# myStrava.net
KiCad netlist of a schematic drawn in EAGLE
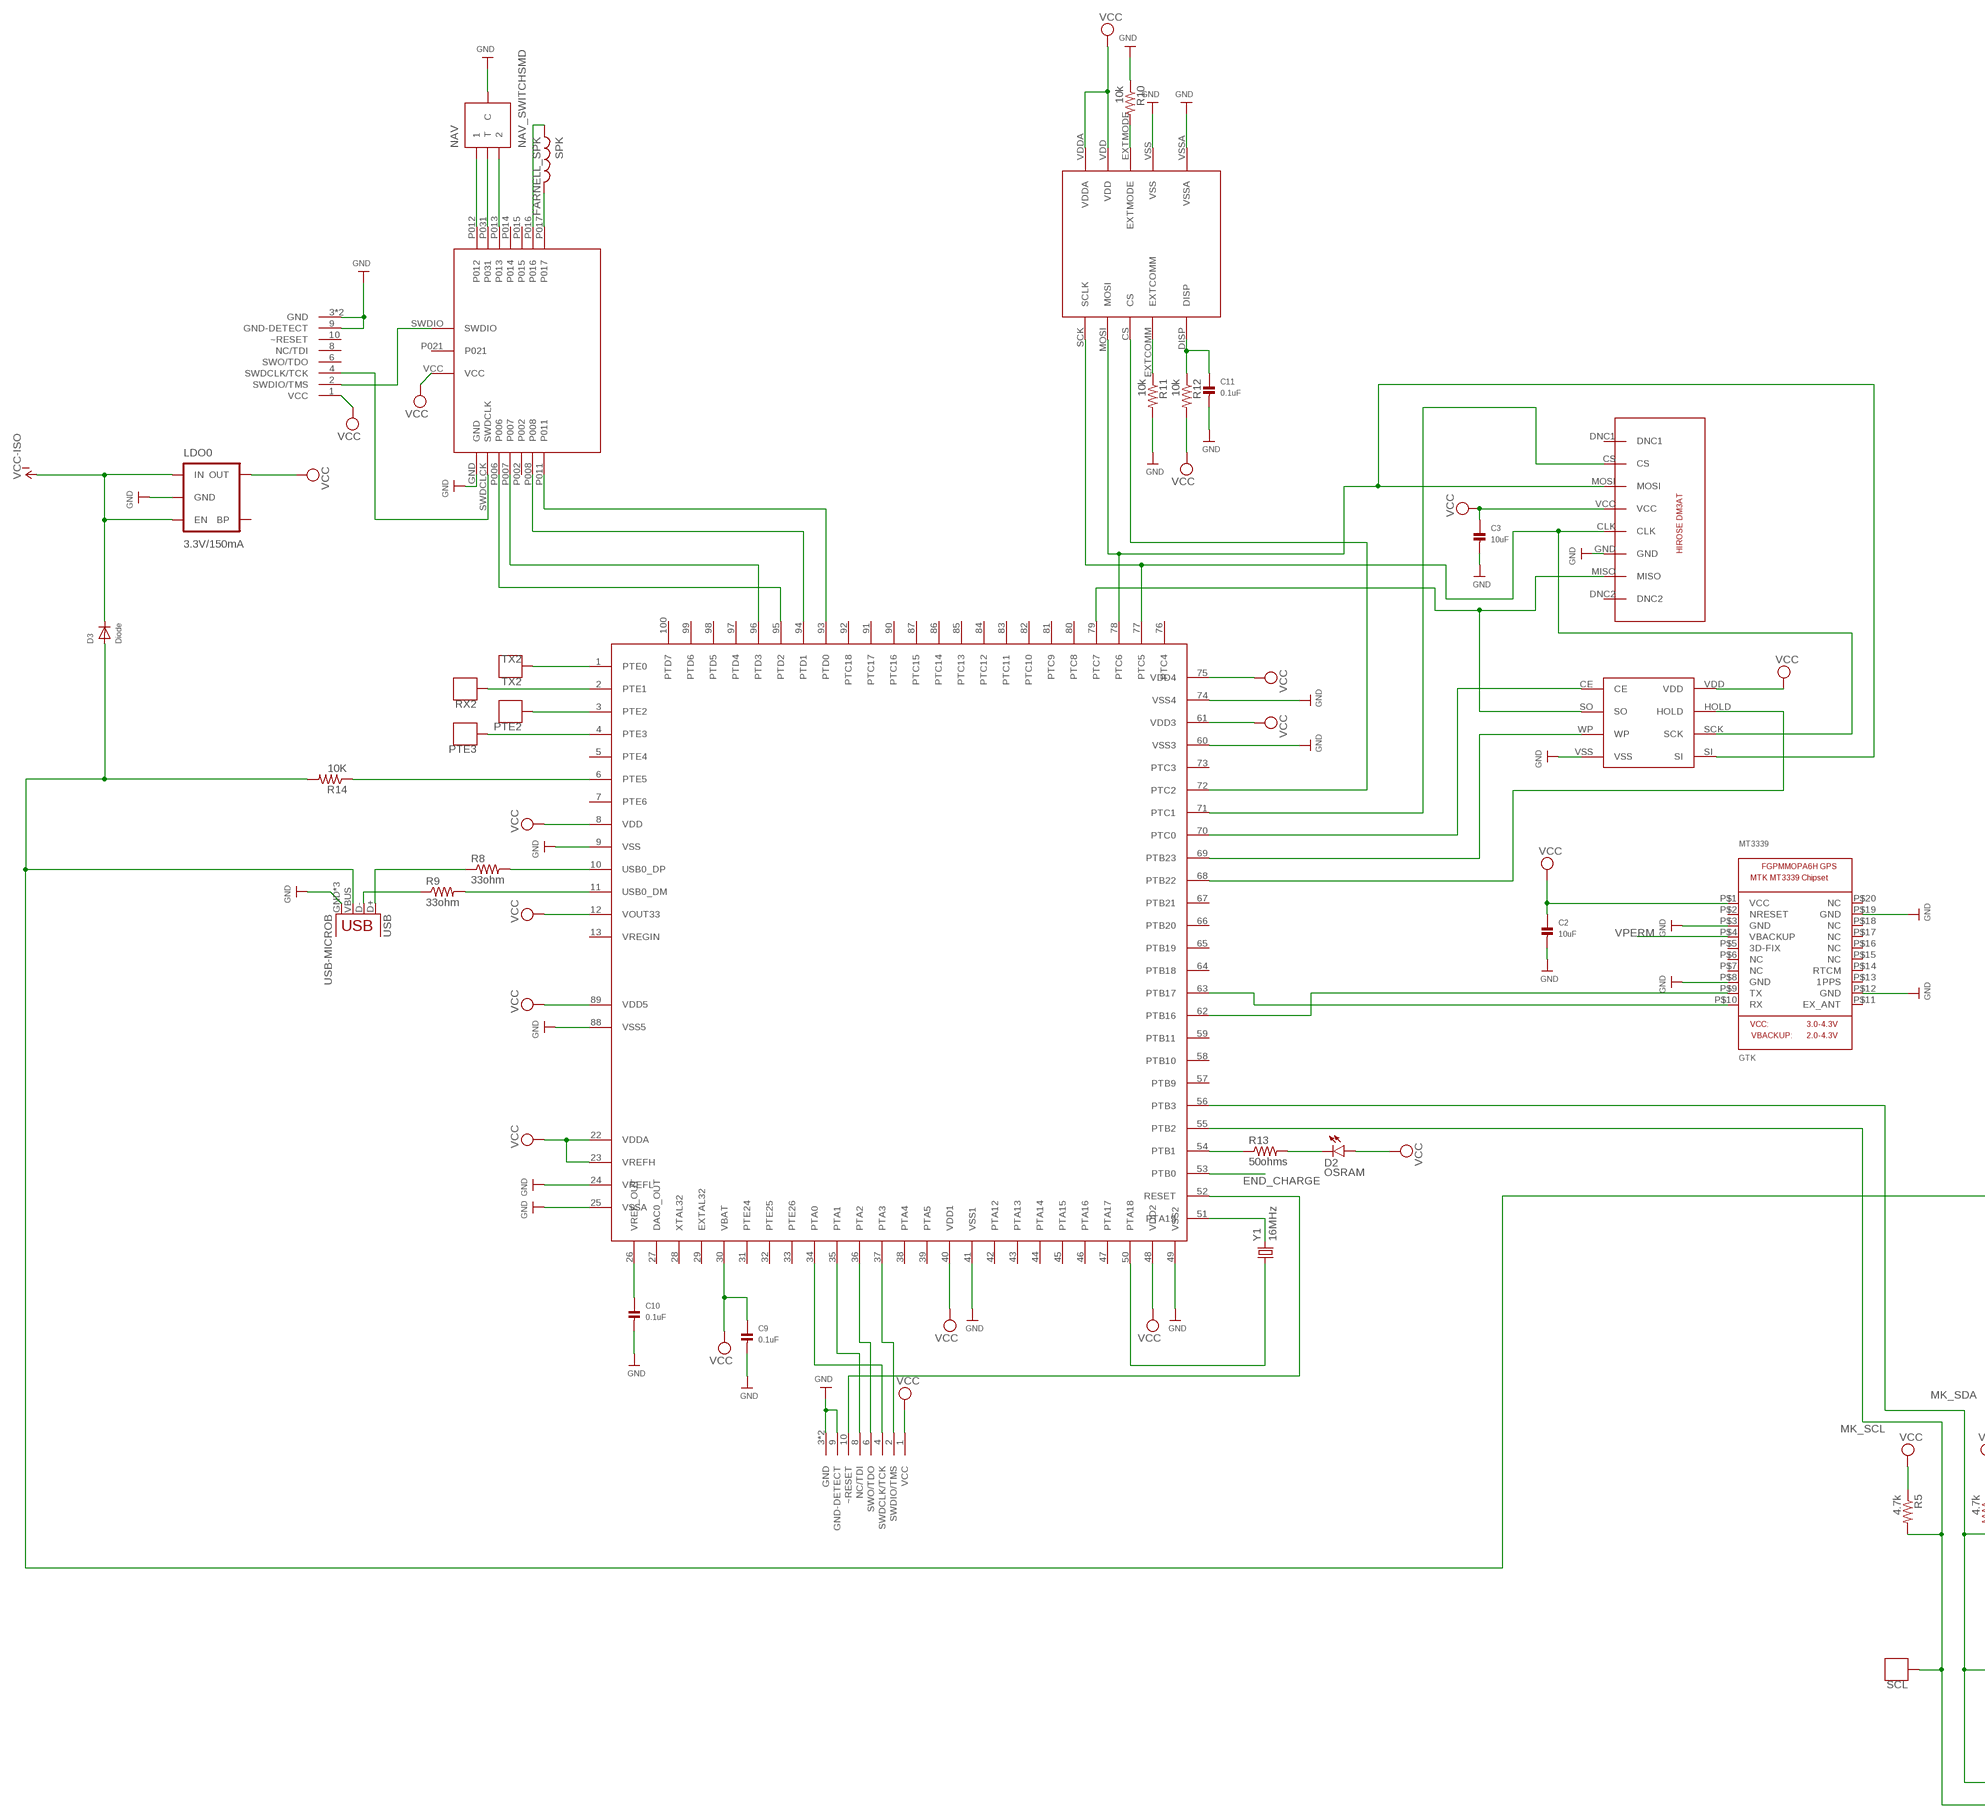
[diagram p0: schematic, sheet 1, part 1 of 2]
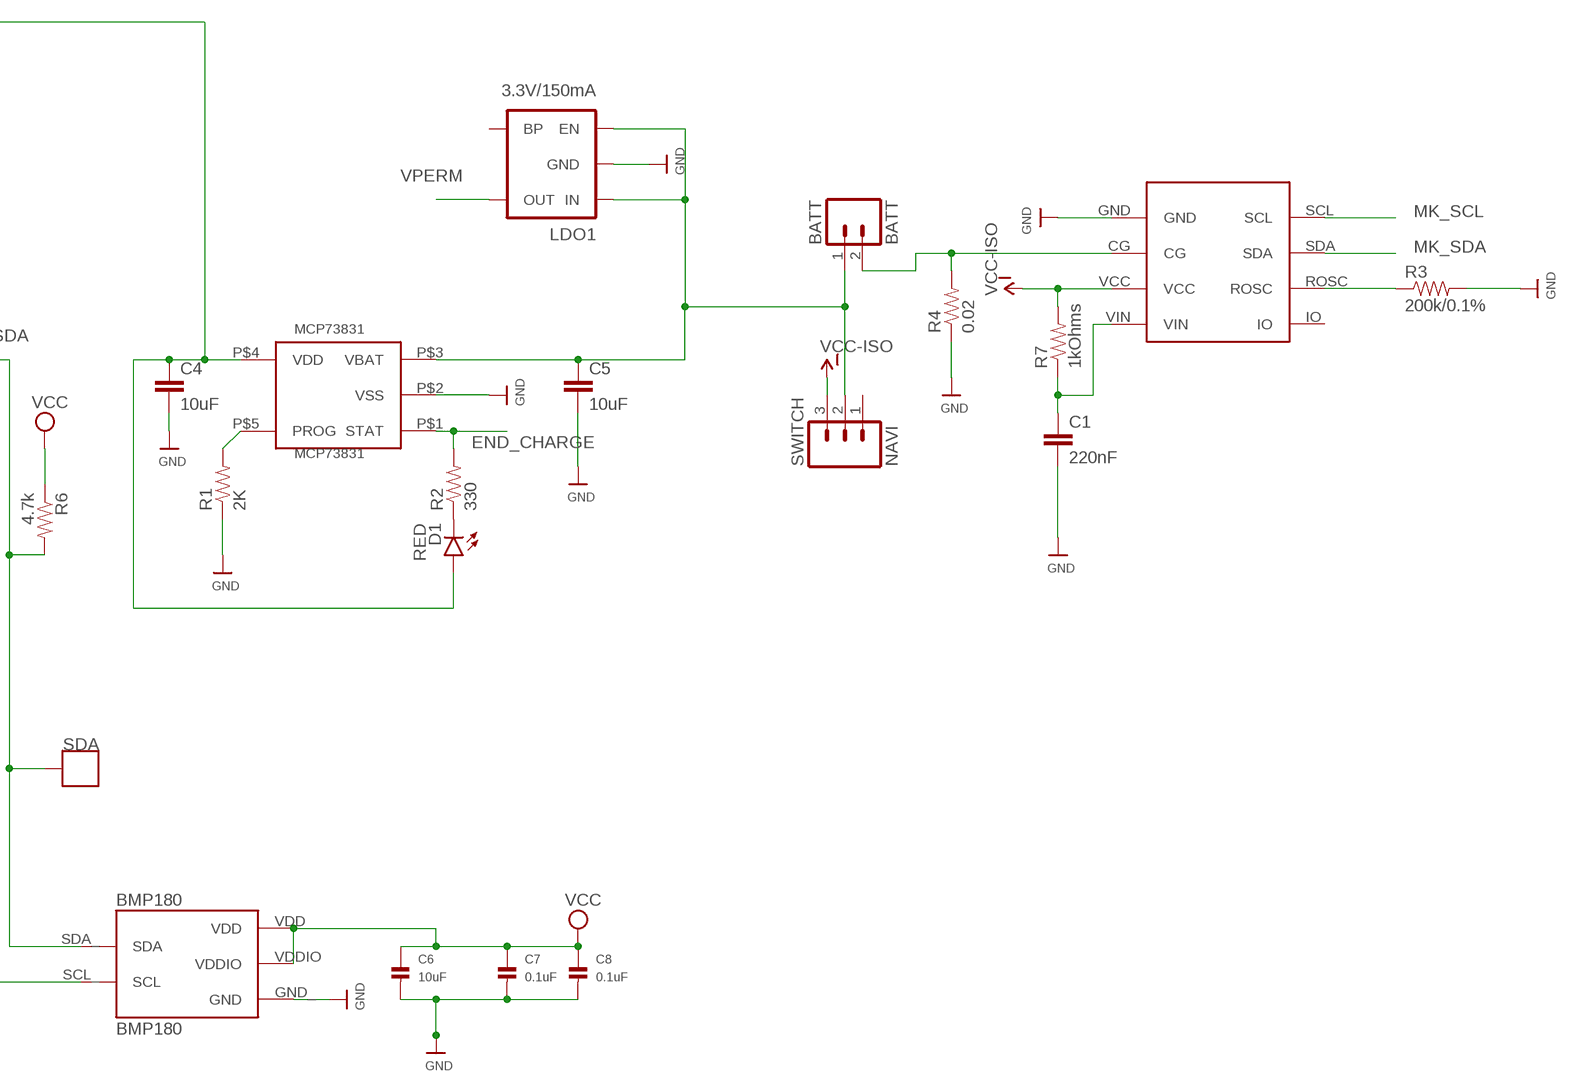
[diagram p1: schematic, sheet 1, part 2 of 2]

(export (version "E")
  (design (tool "Eeschema 10.0.6"))
  (components
    (comp (ref "BATT")
      (value "BATT")
      (footprint "eagle-import:1X02_LONGPADS")
      (libsource (lib "eagle-import") (part "M02PTH3"))
    )
    (comp (ref "BMP180")
      (value "BMP180")
      (footprint "eagle-import:BMP180")
      (libsource (lib "eagle-import") (part "BMP180"))
    )
    (comp (ref "C1")
      (value "220nF")
      (footprint "eagle-import:1206")
      (libsource (lib "eagle-import") (part "10UF-6.3V-20%(1206)"))
    )
    (comp (ref "C2")
      (value "10uF")
      (footprint "eagle-import:1206")
      (libsource (lib "eagle-import") (part "CAP_CERAMIC1206"))
    )
    (comp (ref "C3")
      (value "10uF")
      (footprint "eagle-import:1206")
      (libsource (lib "eagle-import") (part "CAP_CERAMIC1206"))
    )
    (comp (ref "C4")
      (value "10uF")
      (footprint "eagle-import:1206")
      (libsource (lib "eagle-import") (part "10UF-6.3V-20%(1206)"))
    )
    (comp (ref "C5")
      (value "10uF")
      (footprint "eagle-import:1206")
      (libsource (lib "eagle-import") (part "10UF-6.3V-20%(1206)"))
    )
    (comp (ref "C6")
      (value "10uF")
      (footprint "eagle-import:1206")
      (libsource (lib "eagle-import") (part "CAP_CERAMIC1206"))
    )
    (comp (ref "C7")
      (value "0.1uF")
      (footprint "eagle-import:1206")
      (libsource (lib "eagle-import") (part "CAP_CERAMIC1206"))
    )
    (comp (ref "C8")
      (value "0.1uF")
      (footprint "eagle-import:1206")
      (libsource (lib "eagle-import") (part "CAP_CERAMIC1206"))
    )
    (comp (ref "C9")
      (value "0.1uF")
      (footprint "eagle-import:1206")
      (libsource (lib "eagle-import") (part "CAP_CERAMIC1206"))
    )
    (comp (ref "C10")
      (value "0.1uF")
      (footprint "eagle-import:1206")
      (libsource (lib "eagle-import") (part "CAP_CERAMIC1206"))
    )
    (comp (ref "C11")
      (value "0.1uF")
      (footprint "eagle-import:1206")
      (libsource (lib "eagle-import") (part "CAP_CERAMIC1206"))
    )
    (comp (ref "D1")
      (value "RED")
      (footprint "eagle-import:LED-1206")
      (libsource (lib "eagle-import") (part "LED-RED1206"))
    )
    (comp (ref "D2")
      (value "OSRAM")
      (footprint "eagle-import:LED-1206")
      (libsource (lib "eagle-import") (part "LED-RED1206"))
    )
    (comp (ref "D3")
      (value "Diode")
      (footprint "eagle-import:SOD-123FL")
      (libsource (lib "eagle-import") (part "DIODE_SOD-123FL"))
    )
    (comp (ref "JTAG")
      (value "2X5_0.05\"_CORTEX_DEBUGTH_NOKEY_UNSHROUDED")
      (footprint "eagle-import:2X5_0.05__TH_NS")
      (libsource (lib "eagle-import") (part "2X5_0.05{dblquote}_CORTEX_DEBUGTH_NOKEY_UNSHROUDED"))
    )
    (comp (ref "JTAG1")
      (value "2X5_0.05\"_CORTEX_DEBUGTH_NOKEY_UNSHROUDED")
      (footprint "eagle-import:2X5_0.05__TH_NS")
      (libsource (lib "eagle-import") (part "2X5_0.05{dblquote}_CORTEX_DEBUGTH_NOKEY_UNSHROUDED"))
    )
    (comp (ref "LDO0")
      (value "3.3V/150mA")
      (footprint "eagle-import:SOT23-5")
      (libsource (lib "eagle-import") (part "V_REG_MIC52053.3V"))
    )
    (comp (ref "LDO1")
      (value "3.3V/150mA")
      (footprint "eagle-import:SOT23-5")
      (libsource (lib "eagle-import") (part "V_REG_MIC52053.3V"))
    )
    (comp (ref "MCP73831")
      (value "MCP73831")
      (footprint "eagle-import:5PIN_SOT23")
      (libsource (lib "eagle-import") (part "MCP73831"))
    )
    (comp (ref "MK20DN512")
      (value "MK20DN512")
      (footprint "eagle-import:LQFP-100")
      (libsource (lib "eagle-import") (part "MK20DN512"))
    )
    (comp (ref "MT3339")
      (value "GTK")
      (footprint "eagle-import:FGPMMOPA6H")
      (libsource (lib "eagle-import") (part "GPS_FGPMMOPA6H"))
    )
    (comp (ref "N550")
      (value "ANTAP28")
      (footprint "eagle-import:ANTAP")
      (libsource (lib "eagle-import") (part "ANTAP28"))
    )
    (comp (ref "NAV")
      (value "NAV_SWITCHSMD")
      (footprint "eagle-import:NAV_SWITCH")
      (libsource (lib "eagle-import") (part "NAV_SWITCHSMD"))
    )
    (comp (ref "PTE2")
      (value "MDMK2020T4R7MM")
      (footprint "eagle-import:IND-2020")
      (libsource (lib "eagle-import") (part "MDMK2020T4R7MM"))
    )
    (comp (ref "PTE3")
      (value "MDMK2020T4R7MM")
      (footprint "eagle-import:IND-2020")
      (libsource (lib "eagle-import") (part "MDMK2020T4R7MM"))
    )
    (comp (ref "R1")
      (value "2K")
      (footprint "eagle-import:1206")
      (libsource (lib "eagle-import") (part "RESISTOR1206"))
    )
    (comp (ref "R2")
      (value "330")
      (footprint "eagle-import:1206")
      (libsource (lib "eagle-import") (part "RESISTOR1206"))
    )
    (comp (ref "R3")
      (value "200k/0.1%")
      (footprint "eagle-import:1206")
      (libsource (lib "eagle-import") (part "RESISTOR1206"))
    )
    (comp (ref "R4")
      (value "0.02")
      (footprint "eagle-import:1206")
      (libsource (lib "eagle-import") (part "RESISTOR1206"))
    )
    (comp (ref "R5")
      (value "4.7k")
      (footprint "eagle-import:1206")
      (libsource (lib "eagle-import") (part "RESISTOR1206"))
    )
    (comp (ref "R6")
      (value "4.7k")
      (footprint "eagle-import:1206")
      (libsource (lib "eagle-import") (part "RESISTOR1206"))
    )
    (comp (ref "R7")
      (value "1kOhms")
      (footprint "eagle-import:1206")
      (libsource (lib "eagle-import") (part "RESISTOR1206"))
    )
    (comp (ref "R8")
      (value "33ohm")
      (footprint "eagle-import:0805")
      (libsource (lib "eagle-import") (part "RESISTOR0805-RES"))
    )
    (comp (ref "R9")
      (value "33ohm")
      (footprint "eagle-import:0805")
      (libsource (lib "eagle-import") (part "RESISTOR0805-RES"))
    )
    (comp (ref "R10")
      (value "10k")
      (footprint "eagle-import:1206")
      (libsource (lib "eagle-import") (part "RESISTOR1206"))
    )
    (comp (ref "R11")
      (value "10k")
      (footprint "eagle-import:1206")
      (libsource (lib "eagle-import") (part "RESISTOR1206"))
    )
    (comp (ref "R12")
      (value "10k")
      (footprint "eagle-import:1206")
      (libsource (lib "eagle-import") (part "RESISTOR1206"))
    )
    (comp (ref "R13")
      (value "50ohms")
      (footprint "eagle-import:1206")
      (libsource (lib "eagle-import") (part "RESISTOR1206"))
    )
    (comp (ref "R14")
      (value "10K")
      (footprint "eagle-import:1206")
      (libsource (lib "eagle-import") (part "RESISTOR1206"))
    )
    (comp (ref "RX2")
      (value "MDMK2020T4R7MM")
      (footprint "eagle-import:IND-2020")
      (libsource (lib "eagle-import") (part "MDMK2020T4R7MM"))
    )
    (comp (ref "SCL")
      (value "MDMK2020T4R7MM")
      (footprint "eagle-import:IND-2020")
      (libsource (lib "eagle-import") (part "MDMK2020T4R7MM"))
    )
    (comp (ref "SD")
      (value "DM3AT")
      (footprint "eagle-import:DM3AT")
      (libsource (lib "eagle-import") (part "DM3AT"))
    )
    (comp (ref "SDA")
      (value "MDMK2020T4R7MM")
      (footprint "eagle-import:IND-2020")
      (libsource (lib "eagle-import") (part "MDMK2020T4R7MM"))
    )
    (comp (ref "SHARP")
      (value "SHARP27")
      (footprint "eagle-import:SHARP27")
      (libsource (lib "eagle-import") (part "SHARP27"))
    )
    (comp (ref "SPK")
      (value "FARNELL_SPK")
      (footprint "eagle-import:IND-2020")
      (libsource (lib "eagle-import") (part "Strutz Electronic Industries_MDMK2020T4R7MM"))
    )
    (comp (ref "SST25")
      (value "FLASH")
      (footprint "eagle-import:SOIC8")
      (libsource (lib "eagle-import") (part "FLASH"))
    )
    (comp (ref "STC3100")
      (value "STC3100")
      (footprint "eagle-import:STC3100")
      (libsource (lib "eagle-import") (part "STC3100"))
    )
    (comp (ref "SWITCH")
      (value "NAVI")
      (footprint "eagle-import:1X03_LOCK")
      (libsource (lib "eagle-import") (part "M03LOCK"))
    )
    (comp (ref "TX2")
      (value "TX2")
      (footprint "eagle-import:IND-2020")
      (libsource (lib "eagle-import") (part "MDMK2020T4R7MM"))
    )
    (comp (ref "USB")
      (value "USB-MICROB")
      (footprint "eagle-import:USB-MICROB")
      (libsource (lib "eagle-import") (part "USB-MICROB"))
    )
    (comp (ref "Y1")
      (value "16MHz")
      (footprint "eagle-import:HC49U-V")
      (libsource (lib "eagle-import") (part "CRYSTALHC49UV"))
    )
  )
  (nets
    (net (code "1") (name "/END_CHARGE") (class "Default")
      (node (ref "MCP73831") (pin "P$1") (pinfunction "STAT_P$1") (pintype "bidirectional"))
      (node (ref "MK20DN512") (pin "53") (pinfunction "PTB0_53") (pintype "bidirectional"))
      (node (ref "R2") (pin "2") (pinfunction "2_2") (pintype "passive"))
    )
    (net (code "2") (name "/MK_SCL") (class "Default")
      (node (ref "BMP180") (pin "SCL_") (pinfunction "SCL_SCL_") (pintype "input"))
      (node (ref "MK20DN512") (pin "55") (pinfunction "PTB2_55") (pintype "bidirectional"))
      (node (ref "R5") (pin "2") (pinfunction "2_2") (pintype "passive"))
      (node (ref "SCL") (pin "P$1") (pinfunction "1_P$1") (pintype "passive"))
      (node (ref "STC3100") (pin "SCL") (pinfunction "SCL_SCL") (pintype "bidirectional"))
    )
    (net (code "3") (name "/MK_SDA") (class "Default")
      (node (ref "BMP180") (pin "SDA_") (pinfunction "SDA_SDA_") (pintype "bidirectional"))
      (node (ref "MK20DN512") (pin "56") (pinfunction "PTB3_56") (pintype "bidirectional"))
      (node (ref "R6") (pin "2") (pinfunction "2_2") (pintype "passive"))
      (node (ref "SDA") (pin "P$1") (pinfunction "1_P$1") (pintype "passive"))
      (node (ref "STC3100") (pin "SDA") (pinfunction "SDA_SDA") (pintype "bidirectional"))
    )
    (net (code "4") (name "/VPERM") (class "Default")
      (node (ref "LDO1") (pin "5") (pinfunction "OUT_5") (pintype "passive"))
      (node (ref "MT3339") (pin "P$4") (pinfunction "VBACKUP_P$4") (pintype "bidirectional"))
    )
    (net (code "5") (name "GND") (class "Default")
      (node (ref "BMP180") (pin "GND_") (pinfunction "GND_GND_") (pintype "power_in"))
      (node (ref "C1") (pin "2") (pinfunction "2_2") (pintype "passive"))
      (node (ref "C10") (pin "2") (pinfunction "P$2_2") (pintype "passive"))
      (node (ref "C11") (pin "2") (pinfunction "P$2_2") (pintype "passive"))
      (node (ref "C2") (pin "2") (pinfunction "P$2_2") (pintype "passive"))
      (node (ref "C3") (pin "2") (pinfunction "P$2_2") (pintype "passive"))
      (node (ref "C4") (pin "2") (pinfunction "2_2") (pintype "passive"))
      (node (ref "C5") (pin "2") (pinfunction "2_2") (pintype "passive"))
      (node (ref "C6") (pin "2") (pinfunction "P$2_2") (pintype "passive"))
      (node (ref "C7") (pin "2") (pinfunction "P$2_2") (pintype "passive"))
      (node (ref "C8") (pin "2") (pinfunction "P$2_2") (pintype "passive"))
      (node (ref "C9") (pin "2") (pinfunction "P$2_2") (pintype "passive"))
      (node (ref "JTAG") (pin "3") (pinfunction "GND_3") (pintype "bidirectional"))
      (node (ref "JTAG") (pin "5") (pinfunction "GND_5") (pintype "bidirectional"))
      (node (ref "JTAG") (pin "9") (pinfunction "GND-DETECT_9") (pintype "bidirectional"))
      (node (ref "JTAG1") (pin "3") (pinfunction "GND_3") (pintype "bidirectional"))
      (node (ref "JTAG1") (pin "5") (pinfunction "GND_5") (pintype "bidirectional"))
      (node (ref "JTAG1") (pin "9") (pinfunction "GND-DETECT_9") (pintype "bidirectional"))
      (node (ref "LDO0") (pin "2") (pinfunction "GND_2") (pintype "input"))
      (node (ref "LDO1") (pin "2") (pinfunction "GND_2") (pintype "input"))
      (node (ref "MCP73831") (pin "P$2") (pinfunction "VSS_P$2") (pintype "bidirectional"))
      (node (ref "MK20DN512") (pin "24") (pinfunction "VREFL_24") (pintype "bidirectional"))
      (node (ref "MK20DN512") (pin "25") (pinfunction "VSSA_25") (pintype "bidirectional"))
      (node (ref "MK20DN512") (pin "41") (pinfunction "VSS1_41") (pintype "bidirectional"))
      (node (ref "MK20DN512") (pin "49") (pinfunction "VSS2_49") (pintype "bidirectional"))
      (node (ref "MK20DN512") (pin "60") (pinfunction "VSS3_60") (pintype "bidirectional"))
      (node (ref "MK20DN512") (pin "74") (pinfunction "VSS4_74") (pintype "bidirectional"))
      (node (ref "MK20DN512") (pin "88") (pinfunction "VSS5_88") (pintype "bidirectional"))
      (node (ref "MK20DN512") (pin "9") (pinfunction "VSS_9") (pintype "bidirectional"))
      (node (ref "MT3339") (pin "P$12") (pinfunction "GND_P$12") (pintype "bidirectional"))
      (node (ref "MT3339") (pin "P$19") (pinfunction "GND_P$19") (pintype "bidirectional"))
      (node (ref "MT3339") (pin "P$3") (pinfunction "GND_P$3") (pintype "bidirectional"))
      (node (ref "MT3339") (pin "P$8") (pinfunction "GND_P$8") (pintype "bidirectional"))
      (node (ref "N550") (pin "GND") (pinfunction "GND_GND") (pintype "power_in"))
      (node (ref "NAV") (pin "C") (pinfunction "C_C") (pintype "power_in"))
      (node (ref "R1") (pin "1") (pinfunction "1_1") (pintype "passive"))
      (node (ref "R10") (pin "1") (pinfunction "1_1") (pintype "passive"))
      (node (ref "R11") (pin "2") (pinfunction "2_2") (pintype "passive"))
      (node (ref "R3") (pin "2") (pinfunction "2_2") (pintype "passive"))
      (node (ref "R4") (pin "1") (pinfunction "1_1") (pintype "passive"))
      (node (ref "SD") (pin "GND") (pinfunction "GND_GND") (pintype "bidirectional"))
      (node (ref "SHARP") (pin "VSS") (pinfunction "VSS_VSS") (pintype "bidirectional"))
      (node (ref "SHARP") (pin "VSSA") (pinfunction "VSSA_VSSA") (pintype "bidirectional"))
      (node (ref "SST25") (pin "VSS") (pinfunction "VSS_VSS") (pintype "bidirectional"))
      (node (ref "STC3100") (pin "GND") (pinfunction "GND_GND") (pintype "bidirectional"))
      (node (ref "USB") (pin "GND") (pinfunction "GND_GND") (pintype "bidirectional"))
      (node (ref "USB") (pin "MT1") (pinfunction "GND_MT1") (pintype "bidirectional"))
      (node (ref "USB") (pin "MT2") (pinfunction "GND_MT2") (pintype "bidirectional"))
    )
    (net (code "6") (name "Net-(BATT-Pad2)") (class "Default")
      (node (ref "BATT") (pin "2") (pinfunction "2_2") (pintype "passive"))
      (node (ref "R4") (pin "2") (pinfunction "2_2") (pintype "passive"))
      (node (ref "STC3100") (pin "CG") (pinfunction "CG_CG") (pintype "bidirectional"))
    )
    (net (code "7") (name "Net-(C1-Pad1)") (class "Default")
      (node (ref "C1") (pin "1") (pinfunction "1_1") (pintype "passive"))
      (node (ref "R7") (pin "1") (pinfunction "1_1") (pintype "passive"))
      (node (ref "STC3100") (pin "VIN") (pinfunction "VIN_VIN") (pintype "bidirectional"))
    )
    (net (code "8") (name "Net-(C10-P$1)") (class "Default")
      (node (ref "C10") (pin "1") (pinfunction "P$1_1") (pintype "passive"))
      (node (ref "MK20DN512") (pin "26") (pinfunction "VREF_OUT_26") (pintype "bidirectional"))
    )
    (net (code "9") (name "Net-(C11-P$1)") (class "Default")
      (node (ref "C11") (pin "1") (pinfunction "P$1_1") (pintype "passive"))
      (node (ref "R12") (pin "1") (pinfunction "1_1") (pintype "passive"))
      (node (ref "SHARP") (pin "DISP") (pinfunction "DISP_DISP") (pintype "bidirectional"))
    )
    (net (code "10") (name "Net-(D1-PadC)") (class "Default")
      (node (ref "D1") (pin "C") (pinfunction "C_C") (pintype "passive"))
      (node (ref "R2") (pin "1") (pinfunction "1_1") (pintype "passive"))
    )
    (net (code "11") (name "Net-(D2-PadC)") (class "Default")
      (node (ref "D2") (pin "C") (pinfunction "C_C") (pintype "passive"))
      (node (ref "R13") (pin "2") (pinfunction "2_2") (pintype "passive"))
    )
    (net (code "12") (name "Net-(JTAG-NC{slash}TDI)") (class "Default")
      (node (ref "JTAG") (pin "8") (pinfunction "NC/TDI_8") (pintype "bidirectional"))
      (node (ref "MK20DN512") (pin "35") (pinfunction "PTA1_35") (pintype "bidirectional"))
    )
    (net (code "13") (name "Net-(JTAG-SWDCLK{slash}TCK)") (class "Default")
      (node (ref "JTAG") (pin "4") (pinfunction "SWDCLK/TCK_4") (pintype "bidirectional"))
      (node (ref "MK20DN512") (pin "34") (pinfunction "PTA0_34") (pintype "bidirectional"))
    )
    (net (code "14") (name "Net-(JTAG-SWDIO{slash}TMS)") (class "Default")
      (node (ref "JTAG") (pin "2") (pinfunction "SWDIO/TMS_2") (pintype "bidirectional"))
      (node (ref "MK20DN512") (pin "37") (pinfunction "PTA3_37") (pintype "bidirectional"))
    )
    (net (code "15") (name "Net-(JTAG-SWO{slash}TDO)") (class "Default")
      (node (ref "JTAG") (pin "6") (pinfunction "SWO/TDO_6") (pintype "bidirectional"))
      (node (ref "MK20DN512") (pin "36") (pinfunction "PTA2_36") (pintype "bidirectional"))
    )
    (net (code "16") (name "Net-(JTAG-~{RESET})") (class "Default")
      (node (ref "JTAG") (pin "10") (pinfunction "~{RESET}_10") (pintype "bidirectional"))
      (node (ref "MK20DN512") (pin "52") (pinfunction "RESET_52") (pintype "bidirectional"))
    )
    (net (code "17") (name "Net-(JTAG1-SWDCLK{slash}TCK)") (class "Default")
      (node (ref "JTAG1") (pin "4") (pinfunction "SWDCLK/TCK_4") (pintype "bidirectional"))
      (node (ref "N550") (pin "SWDCLCK") (pinfunction "SWDCLK_SWDCLCK") (pintype "bidirectional"))
    )
    (net (code "18") (name "Net-(JTAG1-SWDIO{slash}TMS)") (class "Default")
      (node (ref "JTAG1") (pin "2") (pinfunction "SWDIO/TMS_2") (pintype "bidirectional"))
      (node (ref "N550") (pin "SWDIO") (pinfunction "SWDIO_SWDIO") (pintype "power_in"))
    )
    (net (code "19") (name "Net-(LDO1-EN)") (class "Default")
      (node (ref "BATT") (pin "1") (pinfunction "1_1") (pintype "passive"))
      (node (ref "C5") (pin "1") (pinfunction "1_1") (pintype "passive"))
      (node (ref "LDO1") (pin "1") (pinfunction "IN_1") (pintype "input"))
      (node (ref "LDO1") (pin "3") (pinfunction "EN_3") (pintype "input"))
      (node (ref "MCP73831") (pin "P$3") (pinfunction "VBAT_P$3") (pintype "bidirectional"))
      (node (ref "SWITCH") (pin "2") (pinfunction "2_2") (pintype "passive"))
    )
    (net (code "20") (name "Net-(MCP73831-PROG)") (class "Default")
      (node (ref "MCP73831") (pin "P$5") (pinfunction "PROG_P$5") (pintype "bidirectional"))
      (node (ref "R1") (pin "2") (pinfunction "2_2") (pintype "passive"))
    )
    (net (code "21") (name "Net-(MCP73831-VDD)") (class "Default")
      (node (ref "C4") (pin "1") (pinfunction "1_1") (pintype "passive"))
      (node (ref "D1") (pin "A") (pinfunction "A_A") (pintype "passive"))
      (node (ref "D3") (pin "A") (pinfunction "A_A") (pintype "passive"))
      (node (ref "MCP73831") (pin "P$4") (pinfunction "VDD_P$4") (pintype "bidirectional"))
      (node (ref "R14") (pin "2") (pinfunction "2_2") (pintype "passive"))
      (node (ref "USB") (pin "VBUS") (pinfunction "VBUS_VBUS") (pintype "bidirectional"))
    )
    (net (code "22") (name "Net-(MK20DN512-PTA18)") (class "Default")
      (node (ref "MK20DN512") (pin "50") (pinfunction "PTA18_50") (pintype "bidirectional"))
      (node (ref "Y1") (pin "1") (pinfunction "1_1") (pintype "passive"))
    )
    (net (code "23") (name "Net-(MK20DN512-PTA19)") (class "Default")
      (node (ref "MK20DN512") (pin "51") (pinfunction "PTA19_51") (pintype "bidirectional"))
      (node (ref "Y1") (pin "2") (pinfunction "2_2") (pintype "passive"))
    )
    (net (code "24") (name "Net-(MK20DN512-PTB1)") (class "Default")
      (node (ref "MK20DN512") (pin "54") (pinfunction "PTB1_54") (pintype "bidirectional"))
      (node (ref "R13") (pin "1") (pinfunction "1_1") (pintype "passive"))
    )
    (net (code "25") (name "Net-(MK20DN512-PTB16)") (class "Default")
      (node (ref "MK20DN512") (pin "62") (pinfunction "PTB16_62") (pintype "bidirectional"))
      (node (ref "MT3339") (pin "P$9") (pinfunction "TX_P$9") (pintype "bidirectional"))
    )
    (net (code "26") (name "Net-(MK20DN512-PTB17)") (class "Default")
      (node (ref "MK20DN512") (pin "63") (pinfunction "PTB17_63") (pintype "bidirectional"))
      (node (ref "MT3339") (pin "P$10") (pinfunction "RX_P$10") (pintype "bidirectional"))
    )
    (net (code "27") (name "Net-(MK20DN512-PTB22)") (class "Default")
      (node (ref "MK20DN512") (pin "68") (pinfunction "PTB22_68") (pintype "bidirectional"))
      (node (ref "SST25") (pin "HOLD") (pinfunction "HOLD_HOLD") (pintype "bidirectional"))
    )
    (net (code "28") (name "Net-(MK20DN512-PTB23)") (class "Default")
      (node (ref "MK20DN512") (pin "69") (pinfunction "PTB23_69") (pintype "bidirectional"))
      (node (ref "SST25") (pin "WP") (pinfunction "WP_WP") (pintype "bidirectional"))
    )
    (net (code "29") (name "Net-(MK20DN512-PTC0)") (class "Default")
      (node (ref "MK20DN512") (pin "70") (pinfunction "PTC0_70") (pintype "bidirectional"))
      (node (ref "SST25") (pin "CE") (pinfunction "CE_CE") (pintype "bidirectional"))
    )
    (net (code "30") (name "Net-(MK20DN512-PTC1)") (class "Default")
      (node (ref "MK20DN512") (pin "71") (pinfunction "PTC1_71") (pintype "bidirectional"))
      (node (ref "SD") (pin "CS") (pinfunction "CS_CS") (pintype "bidirectional"))
    )
    (net (code "31") (name "Net-(MK20DN512-PTC2)") (class "Default")
      (node (ref "MK20DN512") (pin "72") (pinfunction "PTC2_72") (pintype "bidirectional"))
      (node (ref "SHARP") (pin "CS") (pinfunction "CS_CS") (pintype "bidirectional"))
    )
    (net (code "32") (name "Net-(MK20DN512-PTC5)") (class "Default")
      (node (ref "MK20DN512") (pin "77") (pinfunction "PTC5_77") (pintype "bidirectional"))
      (node (ref "SD") (pin "CLK") (pinfunction "CLK_CLK") (pintype "bidirectional"))
      (node (ref "SHARP") (pin "SCK") (pinfunction "SCLK_SCK") (pintype "bidirectional"))
      (node (ref "SST25") (pin "SCK") (pinfunction "SCK_SCK") (pintype "bidirectional"))
    )
    (net (code "33") (name "Net-(MK20DN512-PTC6)") (class "Default")
      (node (ref "MK20DN512") (pin "78") (pinfunction "PTC6_78") (pintype "bidirectional"))
      (node (ref "SD") (pin "MOSI") (pinfunction "MOSI_MOSI") (pintype "bidirectional"))
      (node (ref "SHARP") (pin "MOSI") (pinfunction "MOSI_MOSI") (pintype "bidirectional"))
      (node (ref "SST25") (pin "SI") (pinfunction "SI_SI") (pintype "bidirectional"))
    )
    (net (code "34") (name "Net-(MK20DN512-PTC7)") (class "Default")
      (node (ref "MK20DN512") (pin "79") (pinfunction "PTC7_79") (pintype "bidirectional"))
      (node (ref "SD") (pin "MISO") (pinfunction "MISO_MISO") (pintype "bidirectional"))
      (node (ref "SST25") (pin "SO") (pinfunction "SO_SO") (pintype "bidirectional"))
    )
    (net (code "35") (name "Net-(MK20DN512-PTD0)") (class "Default")
      (node (ref "MK20DN512") (pin "93") (pinfunction "PTD0_93") (pintype "bidirectional"))
      (node (ref "N550") (pin "P011") (pinfunction "P011_P011") (pintype "bidirectional"))
    )
    (net (code "36") (name "Net-(MK20DN512-PTD1)") (class "Default")
      (node (ref "MK20DN512") (pin "94") (pinfunction "PTD1_94") (pintype "bidirectional"))
      (node (ref "N550") (pin "P008") (pinfunction "P008_P008") (pintype "bidirectional"))
    )
    (net (code "37") (name "Net-(MK20DN512-PTD2)") (class "Default")
      (node (ref "MK20DN512") (pin "95") (pinfunction "PTD2_95") (pintype "bidirectional"))
      (node (ref "N550") (pin "P006") (pinfunction "P006_P006") (pintype "bidirectional"))
    )
    (net (code "38") (name "Net-(MK20DN512-PTD3)") (class "Default")
      (node (ref "MK20DN512") (pin "96") (pinfunction "PTD3_96") (pintype "bidirectional"))
      (node (ref "N550") (pin "P007") (pinfunction "P007_P007") (pintype "bidirectional"))
    )
    (net (code "39") (name "Net-(MK20DN512-PTE0)") (class "Default")
      (node (ref "MK20DN512") (pin "1") (pinfunction "PTE0_1") (pintype "bidirectional"))
      (node (ref "TX2") (pin "P$1") (pinfunction "1_P$1") (pintype "passive"))
    )
    (net (code "40") (name "Net-(MK20DN512-PTE1)") (class "Default")
      (node (ref "MK20DN512") (pin "2") (pinfunction "PTE1_2") (pintype "bidirectional"))
      (node (ref "RX2") (pin "P$1") (pinfunction "1_P$1") (pintype "passive"))
    )
    (net (code "41") (name "Net-(MK20DN512-PTE2)") (class "Default")
      (node (ref "MK20DN512") (pin "3") (pinfunction "PTE2_3") (pintype "bidirectional"))
      (node (ref "PTE2") (pin "P$1") (pinfunction "1_P$1") (pintype "passive"))
    )
    (net (code "42") (name "Net-(MK20DN512-PTE3)") (class "Default")
      (node (ref "MK20DN512") (pin "4") (pinfunction "PTE3_4") (pintype "bidirectional"))
      (node (ref "PTE3") (pin "P$1") (pinfunction "1_P$1") (pintype "passive"))
    )
    (net (code "43") (name "Net-(MK20DN512-PTE5)") (class "Default")
      (node (ref "MK20DN512") (pin "6") (pinfunction "PTE5_6") (pintype "bidirectional"))
      (node (ref "R14") (pin "1") (pinfunction "1_1") (pintype "passive"))
    )
    (net (code "44") (name "Net-(MK20DN512-USB0_DM)") (class "Default")
      (node (ref "MK20DN512") (pin "11") (pinfunction "USB0_DM_11") (pintype "bidirectional"))
      (node (ref "R9") (pin "2") (pinfunction "2_2") (pintype "passive"))
    )
    (net (code "45") (name "Net-(MK20DN512-USB0_DP)") (class "Default")
      (node (ref "MK20DN512") (pin "10") (pinfunction "USB0_DP_10") (pintype "bidirectional"))
      (node (ref "R8") (pin "2") (pinfunction "2_2") (pintype "passive"))
    )
    (net (code "46") (name "Net-(N550-PadP012)") (class "Default")
      (node (ref "N550") (pin "P012") (pinfunction "P012_P012") (pintype "bidirectional"))
      (node (ref "NAV") (pin "1") (pinfunction "1_1") (pintype "input"))
    )
    (net (code "47") (name "Net-(N550-PadP013)") (class "Default")
      (node (ref "N550") (pin "P013") (pinfunction "P013_P013") (pintype "bidirectional"))
      (node (ref "NAV") (pin "2") (pinfunction "2_2") (pintype "input"))
    )
    (net (code "48") (name "Net-(N550-PadP031)") (class "Default")
      (node (ref "N550") (pin "P031") (pinfunction "P031_P031") (pintype "bidirectional"))
      (node (ref "NAV") (pin "T") (pinfunction "T_T") (pintype "input"))
    )
    (net (code "49") (name "Net-(R3-Pad1)") (class "Default")
      (node (ref "R3") (pin "1") (pinfunction "1_1") (pintype "passive"))
      (node (ref "STC3100") (pin "ROSC") (pinfunction "ROSC_ROSC") (pintype "bidirectional"))
    )
    (net (code "50") (name "Net-(R8-Pad1)") (class "Default")
      (node (ref "R8") (pin "1") (pinfunction "1_1") (pintype "passive"))
      (node (ref "USB") (pin "D+") (pinfunction "D+_D+") (pintype "bidirectional"))
    )
    (net (code "51") (name "Net-(R9-Pad1)") (class "Default")
      (node (ref "R9") (pin "1") (pinfunction "1_1") (pintype "passive"))
      (node (ref "USB") (pin "D-") (pinfunction "D-_D-") (pintype "bidirectional"))
    )
    (net (code "52") (name "Net-(R10-Pad2)") (class "Default")
      (node (ref "R10") (pin "2") (pinfunction "2_2") (pintype "passive"))
      (node (ref "SHARP") (pin "EXTMODE") (pinfunction "EXTMODE_EXTMODE") (pintype "bidirectional"))
    )
    (net (code "53") (name "Net-(R11-Pad1)") (class "Default")
      (node (ref "R11") (pin "1") (pinfunction "1_1") (pintype "passive"))
      (node (ref "SHARP") (pin "EXTCOMM") (pinfunction "EXTCOMM_EXTCOMM") (pintype "bidirectional"))
    )
    (net (code "54") (name "Net-(SPK-1)") (class "Default")
      (node (ref "N550") (pin "P016") (pinfunction "P016_P016") (pintype "input"))
      (node (ref "SPK") (pin "P$1") (pinfunction "1_P$1") (pintype "passive"))
    )
    (net (code "55") (name "Net-(SPK-2)") (class "Default")
      (node (ref "N550") (pin "P017") (pinfunction "P017_P017") (pintype "output"))
      (node (ref "SPK") (pin "P$2") (pinfunction "2_P$2") (pintype "passive"))
    )
    (net (code "56") (name "VCC") (class "Default")
      (node (ref "BMP180") (pin "VDD") (pinfunction "VDD_VDD") (pintype "power_in"))
      (node (ref "BMP180") (pin "VDDIO") (pinfunction "VDDIO_VDDIO") (pintype "power_in"))
      (node (ref "C2") (pin "1") (pinfunction "P$1_1") (pintype "passive"))
      (node (ref "C3") (pin "1") (pinfunction "P$1_1") (pintype "passive"))
      (node (ref "C6") (pin "1") (pinfunction "P$1_1") (pintype "passive"))
      (node (ref "C7") (pin "1") (pinfunction "P$1_1") (pintype "passive"))
      (node (ref "C8") (pin "1") (pinfunction "P$1_1") (pintype "passive"))
      (node (ref "C9") (pin "1") (pinfunction "P$1_1") (pintype "passive"))
      (node (ref "D2") (pin "A") (pinfunction "A_A") (pintype "passive"))
      (node (ref "JTAG") (pin "1") (pinfunction "VCC_1") (pintype "bidirectional"))
      (node (ref "JTAG1") (pin "1") (pinfunction "VCC_1") (pintype "bidirectional"))
      (node (ref "LDO0") (pin "5") (pinfunction "OUT_5") (pintype "passive"))
      (node (ref "MK20DN512") (pin "12") (pinfunction "VOUT33_12") (pintype "bidirectional"))
      (node (ref "MK20DN512") (pin "22") (pinfunction "VDDA_22") (pintype "bidirectional"))
      (node (ref "MK20DN512") (pin "23") (pinfunction "VREFH_23") (pintype "bidirectional"))
      (node (ref "MK20DN512") (pin "30") (pinfunction "VBAT_30") (pintype "bidirectional"))
      (node (ref "MK20DN512") (pin "40") (pinfunction "VDD1_40") (pintype "bidirectional"))
      (node (ref "MK20DN512") (pin "48") (pinfunction "VDD2_48") (pintype "bidirectional"))
      (node (ref "MK20DN512") (pin "61") (pinfunction "VDD3_61") (pintype "bidirectional"))
      (node (ref "MK20DN512") (pin "75") (pinfunction "VDD4_75") (pintype "bidirectional"))
      (node (ref "MK20DN512") (pin "8") (pinfunction "VDD_8") (pintype "bidirectional"))
      (node (ref "MK20DN512") (pin "89") (pinfunction "VDD5_89") (pintype "bidirectional"))
      (node (ref "MT3339") (pin "P$1") (pinfunction "VCC_P$1") (pintype "bidirectional"))
      (node (ref "N550") (pin "VCC") (pinfunction "VCC_VCC") (pintype "power_in"))
      (node (ref "R12") (pin "2") (pinfunction "2_2") (pintype "passive"))
      (node (ref "R5") (pin "1") (pinfunction "1_1") (pintype "passive"))
      (node (ref "R6") (pin "1") (pinfunction "1_1") (pintype "passive"))
      (node (ref "SD") (pin "VCC") (pinfunction "VCC_VCC") (pintype "bidirectional"))
      (node (ref "SHARP") (pin "VDD") (pinfunction "VDD_VDD") (pintype "bidirectional"))
      (node (ref "SHARP") (pin "VDDA") (pinfunction "VDDA_VDDA") (pintype "bidirectional"))
      (node (ref "SST25") (pin "VDD") (pinfunction "VDD_VDD") (pintype "bidirectional"))
    )
    (net (code "57") (name "VCC-ISO") (class "Default")
      (node (ref "D3") (pin "C") (pinfunction "C_C") (pintype "passive"))
      (node (ref "LDO0") (pin "1") (pinfunction "IN_1") (pintype "input"))
      (node (ref "LDO0") (pin "3") (pinfunction "EN_3") (pintype "input"))
      (node (ref "R7") (pin "2") (pinfunction "2_2") (pintype "passive"))
      (node (ref "STC3100") (pin "VCC") (pinfunction "VCC_VCC") (pintype "bidirectional"))
      (node (ref "SWITCH") (pin "3") (pinfunction "3_3") (pintype "passive"))
    )
    (net (code "58") (name "unconnected-(JTAG1-NC{slash}TDI-Pad8)") (class "Default")
      (node (ref "JTAG1") (pin "8") (pinfunction "NC/TDI_8") (pintype "bidirectional"))
    )
    (net (code "59") (name "unconnected-(JTAG1-SWO{slash}TDO-Pad6)") (class "Default")
      (node (ref "JTAG1") (pin "6") (pinfunction "SWO/TDO_6") (pintype "bidirectional"))
    )
    (net (code "60") (name "unconnected-(JTAG1-~{RESET}-Pad10)") (class "Default")
      (node (ref "JTAG1") (pin "10") (pinfunction "~{RESET}_10") (pintype "bidirectional"))
    )
    (net (code "61") (name "unconnected-(LDO0-BP-Pad4)") (class "Default")
      (node (ref "LDO0") (pin "4") (pinfunction "BP_4") (pintype "input"))
    )
    (net (code "62") (name "unconnected-(LDO1-BP-Pad4)") (class "Default")
      (node (ref "LDO1") (pin "4") (pinfunction "BP_4") (pintype "input"))
    )
    (net (code "63") (name "unconnected-(MK20DN512-DAC0_OUT-Pad27)") (class "Default")
      (node (ref "MK20DN512") (pin "27") (pinfunction "DAC0_OUT_27") (pintype "bidirectional"))
    )
    (net (code "64") (name "unconnected-(MK20DN512-EXTAL32-Pad29)") (class "Default")
      (node (ref "MK20DN512") (pin "29") (pinfunction "EXTAL32_29") (pintype "bidirectional"))
    )
    (net (code "65") (name "unconnected-(MK20DN512-PTA4-Pad38)") (class "Default")
      (node (ref "MK20DN512") (pin "38") (pinfunction "PTA4_38") (pintype "bidirectional"))
    )
    (net (code "66") (name "unconnected-(MK20DN512-PTA5-Pad39)") (class "Default")
      (node (ref "MK20DN512") (pin "39") (pinfunction "PTA5_39") (pintype "bidirectional"))
    )
    (net (code "67") (name "unconnected-(MK20DN512-PTA12-Pad42)") (class "Default")
      (node (ref "MK20DN512") (pin "42") (pinfunction "PTA12_42") (pintype "bidirectional"))
    )
    (net (code "68") (name "unconnected-(MK20DN512-PTA13-Pad43)") (class "Default")
      (node (ref "MK20DN512") (pin "43") (pinfunction "PTA13_43") (pintype "bidirectional"))
    )
    (net (code "69") (name "unconnected-(MK20DN512-PTA14-Pad44)") (class "Default")
      (node (ref "MK20DN512") (pin "44") (pinfunction "PTA14_44") (pintype "bidirectional"))
    )
    (net (code "70") (name "unconnected-(MK20DN512-PTA15-Pad45)") (class "Default")
      (node (ref "MK20DN512") (pin "45") (pinfunction "PTA15_45") (pintype "bidirectional"))
    )
    (net (code "71") (name "unconnected-(MK20DN512-PTA16-Pad46)") (class "Default")
      (node (ref "MK20DN512") (pin "46") (pinfunction "PTA16_46") (pintype "bidirectional"))
    )
    (net (code "72") (name "unconnected-(MK20DN512-PTA17-Pad47)") (class "Default")
      (node (ref "MK20DN512") (pin "47") (pinfunction "PTA17_47") (pintype "bidirectional"))
    )
    (net (code "73") (name "unconnected-(MK20DN512-PTB9-Pad57)") (class "Default")
      (node (ref "MK20DN512") (pin "57") (pinfunction "PTB9_57") (pintype "bidirectional"))
    )
    (net (code "74") (name "unconnected-(MK20DN512-PTB10-Pad58)") (class "Default")
      (node (ref "MK20DN512") (pin "58") (pinfunction "PTB10_58") (pintype "bidirectional"))
    )
    (net (code "75") (name "unconnected-(MK20DN512-PTB11-Pad59)") (class "Default")
      (node (ref "MK20DN512") (pin "59") (pinfunction "PTB11_59") (pintype "bidirectional"))
    )
    (net (code "76") (name "unconnected-(MK20DN512-PTB18-Pad64)") (class "Default")
      (node (ref "MK20DN512") (pin "64") (pinfunction "PTB18_64") (pintype "bidirectional"))
    )
    (net (code "77") (name "unconnected-(MK20DN512-PTB19-Pad65)") (class "Default")
      (node (ref "MK20DN512") (pin "65") (pinfunction "PTB19_65") (pintype "bidirectional"))
    )
    (net (code "78") (name "unconnected-(MK20DN512-PTB20-Pad66)") (class "Default")
      (node (ref "MK20DN512") (pin "66") (pinfunction "PTB20_66") (pintype "bidirectional"))
    )
    (net (code "79") (name "unconnected-(MK20DN512-PTB21-Pad67)") (class "Default")
      (node (ref "MK20DN512") (pin "67") (pinfunction "PTB21_67") (pintype "bidirectional"))
    )
    (net (code "80") (name "unconnected-(MK20DN512-PTC3-Pad73)") (class "Default")
      (node (ref "MK20DN512") (pin "73") (pinfunction "PTC3_73") (pintype "bidirectional"))
    )
    (net (code "81") (name "unconnected-(MK20DN512-PTC4-Pad76)") (class "Default")
      (node (ref "MK20DN512") (pin "76") (pinfunction "PTC4_76") (pintype "bidirectional"))
    )
    (net (code "82") (name "unconnected-(MK20DN512-PTC8-Pad80)") (class "Default")
      (node (ref "MK20DN512") (pin "80") (pinfunction "PTC8_80") (pintype "bidirectional"))
    )
    (net (code "83") (name "unconnected-(MK20DN512-PTC9-Pad81)") (class "Default")
      (node (ref "MK20DN512") (pin "81") (pinfunction "PTC9_81") (pintype "bidirectional"))
    )
    (net (code "84") (name "unconnected-(MK20DN512-PTC10-Pad82)") (class "Default")
      (node (ref "MK20DN512") (pin "82") (pinfunction "PTC10_82") (pintype "bidirectional"))
    )
    (net (code "85") (name "unconnected-(MK20DN512-PTC11-Pad83)") (class "Default")
      (node (ref "MK20DN512") (pin "83") (pinfunction "PTC11_83") (pintype "bidirectional"))
    )
    (net (code "86") (name "unconnected-(MK20DN512-PTC12-Pad84)") (class "Default")
      (node (ref "MK20DN512") (pin "84") (pinfunction "PTC12_84") (pintype "bidirectional"))
    )
    (net (code "87") (name "unconnected-(MK20DN512-PTC13-Pad85)") (class "Default")
      (node (ref "MK20DN512") (pin "85") (pinfunction "PTC13_85") (pintype "bidirectional"))
    )
    (net (code "88") (name "unconnected-(MK20DN512-PTC14-Pad86)") (class "Default")
      (node (ref "MK20DN512") (pin "86") (pinfunction "PTC14_86") (pintype "bidirectional"))
    )
    (net (code "89") (name "unconnected-(MK20DN512-PTC15-Pad87)") (class "Default")
      (node (ref "MK20DN512") (pin "87") (pinfunction "PTC15_87") (pintype "bidirectional"))
    )
    (net (code "90") (name "unconnected-(MK20DN512-PTC16-Pad90)") (class "Default")
      (node (ref "MK20DN512") (pin "90") (pinfunction "PTC16_90") (pintype "bidirectional"))
    )
    (net (code "91") (name "unconnected-(MK20DN512-PTC17-Pad91)") (class "Default")
      (node (ref "MK20DN512") (pin "91") (pinfunction "PTC17_91") (pintype "bidirectional"))
    )
    (net (code "92") (name "unconnected-(MK20DN512-PTC18-Pad92)") (class "Default")
      (node (ref "MK20DN512") (pin "92") (pinfunction "PTC18_92") (pintype "bidirectional"))
    )
    (net (code "93") (name "unconnected-(MK20DN512-PTD4-Pad97)") (class "Default")
      (node (ref "MK20DN512") (pin "97") (pinfunction "PTD4_97") (pintype "bidirectional"))
    )
    (net (code "94") (name "unconnected-(MK20DN512-PTD5-Pad98)") (class "Default")
      (node (ref "MK20DN512") (pin "98") (pinfunction "PTD5_98") (pintype "bidirectional"))
    )
    (net (code "95") (name "unconnected-(MK20DN512-PTD6-Pad99)") (class "Default")
      (node (ref "MK20DN512") (pin "99") (pinfunction "PTD6_99") (pintype "bidirectional"))
    )
    (net (code "96") (name "unconnected-(MK20DN512-PTD7-Pad100)") (class "Default")
      (node (ref "MK20DN512") (pin "100") (pinfunction "PTD7_100") (pintype "bidirectional"))
    )
    (net (code "97") (name "unconnected-(MK20DN512-PTE4-Pad5)") (class "Default")
      (node (ref "MK20DN512") (pin "5") (pinfunction "PTE4_5") (pintype "bidirectional"))
    )
    (net (code "98") (name "unconnected-(MK20DN512-PTE6-Pad7)") (class "Default")
      (node (ref "MK20DN512") (pin "7") (pinfunction "PTE6_7") (pintype "bidirectional"))
    )
    (net (code "99") (name "unconnected-(MK20DN512-PTE24-Pad31)") (class "Default")
      (node (ref "MK20DN512") (pin "31") (pinfunction "PTE24_31") (pintype "bidirectional"))
    )
    (net (code "100") (name "unconnected-(MK20DN512-PTE25-Pad32)") (class "Default")
      (node (ref "MK20DN512") (pin "32") (pinfunction "PTE25_32") (pintype "bidirectional"))
    )
    (net (code "101") (name "unconnected-(MK20DN512-PTE26-Pad33)") (class "Default")
      (node (ref "MK20DN512") (pin "33") (pinfunction "PTE26_33") (pintype "bidirectional"))
    )
    (net (code "102") (name "unconnected-(MK20DN512-VREGIN-Pad13)") (class "Default")
      (node (ref "MK20DN512") (pin "13") (pinfunction "VREGIN_13") (pintype "bidirectional"))
    )
    (net (code "103") (name "unconnected-(MK20DN512-XTAL32-Pad28)") (class "Default")
      (node (ref "MK20DN512") (pin "28") (pinfunction "XTAL32_28") (pintype "bidirectional"))
    )
    (net (code "104") (name "unconnected-(MT3339-1PPS-PadP$13)") (class "Default")
      (node (ref "MT3339") (pin "P$13") (pinfunction "1PPS_P$13") (pintype "bidirectional"))
    )
    (net (code "105") (name "unconnected-(MT3339-3D-FIX-PadP$5)") (class "Default")
      (node (ref "MT3339") (pin "P$5") (pinfunction "3D-FIX_P$5") (pintype "bidirectional"))
    )
    (net (code "106") (name "unconnected-(MT3339-EX_ANT-PadP$11)") (class "Default")
      (node (ref "MT3339") (pin "P$11") (pinfunction "EX_ANT_P$11") (pintype "bidirectional"))
    )
    (net (code "107") (name "unconnected-(MT3339-NC-PadP$6)") (class "Default")
      (node (ref "MT3339") (pin "P$6") (pinfunction "NC_P$6") (pintype "bidirectional"))
    )
    (net (code "108") (name "unconnected-(MT3339-NC-PadP$7)") (class "Default")
      (node (ref "MT3339") (pin "P$7") (pinfunction "NC_P$7") (pintype "bidirectional"))
    )
    (net (code "109") (name "unconnected-(MT3339-NC-PadP$15)") (class "Default")
      (node (ref "MT3339") (pin "P$15") (pinfunction "NC_P$15") (pintype "bidirectional"))
    )
    (net (code "110") (name "unconnected-(MT3339-NC-PadP$16)") (class "Default")
      (node (ref "MT3339") (pin "P$16") (pinfunction "NC_P$16") (pintype "bidirectional"))
    )
    (net (code "111") (name "unconnected-(MT3339-NC-PadP$17)") (class "Default")
      (node (ref "MT3339") (pin "P$17") (pinfunction "NC_P$17") (pintype "bidirectional"))
    )
    (net (code "112") (name "unconnected-(MT3339-NC-PadP$18)") (class "Default")
      (node (ref "MT3339") (pin "P$18") (pinfunction "NC_P$18") (pintype "bidirectional"))
    )
    (net (code "113") (name "unconnected-(MT3339-NC-PadP$20)") (class "Default")
      (node (ref "MT3339") (pin "P$20") (pinfunction "NC_P$20") (pintype "bidirectional"))
    )
    (net (code "114") (name "unconnected-(MT3339-NRESET-PadP$2)") (class "Default")
      (node (ref "MT3339") (pin "P$2") (pinfunction "NRESET_P$2") (pintype "bidirectional"))
    )
    (net (code "115") (name "unconnected-(MT3339-RTCM-PadP$14)") (class "Default")
      (node (ref "MT3339") (pin "P$14") (pinfunction "RTCM_P$14") (pintype "bidirectional"))
    )
    (net (code "116") (name "unconnected-(N550-PadP002)") (class "Default")
      (node (ref "N550") (pin "P002") (pinfunction "P002_P002") (pintype "bidirectional"))
    )
    (net (code "117") (name "unconnected-(N550-PadP014)") (class "Default")
      (node (ref "N550") (pin "P014") (pinfunction "P014_P014") (pintype "bidirectional"))
    )
    (net (code "118") (name "unconnected-(N550-PadP015)") (class "Default")
      (node (ref "N550") (pin "P015") (pinfunction "P015_P015") (pintype "bidirectional"))
    )
    (net (code "119") (name "unconnected-(N550-PadP021)") (class "Default")
      (node (ref "N550") (pin "P021") (pinfunction "P021_P021") (pintype "bidirectional"))
    )
    (net (code "120") (name "unconnected-(SD-PadDNC1)") (class "Default")
      (node (ref "SD") (pin "DNC1") (pinfunction "DNC1_DNC1") (pintype "bidirectional"))
    )
    (net (code "121") (name "unconnected-(SD-PadDNC2)") (class "Default")
      (node (ref "SD") (pin "DNC2") (pinfunction "DNC2_DNC2") (pintype "bidirectional"))
    )
    (net (code "122") (name "unconnected-(STC3100-PadIO)") (class "Default")
      (node (ref "STC3100") (pin "IO") (pinfunction "IO_IO") (pintype "bidirectional"))
    )
    (net (code "123") (name "unconnected-(SWITCH-Pad1)") (class "Default")
      (node (ref "SWITCH") (pin "1") (pinfunction "1_1") (pintype "passive"))
    )
  )
)
